# MRDT0002A1.net
KiCad netlist of a schematic drawn in EAGLE
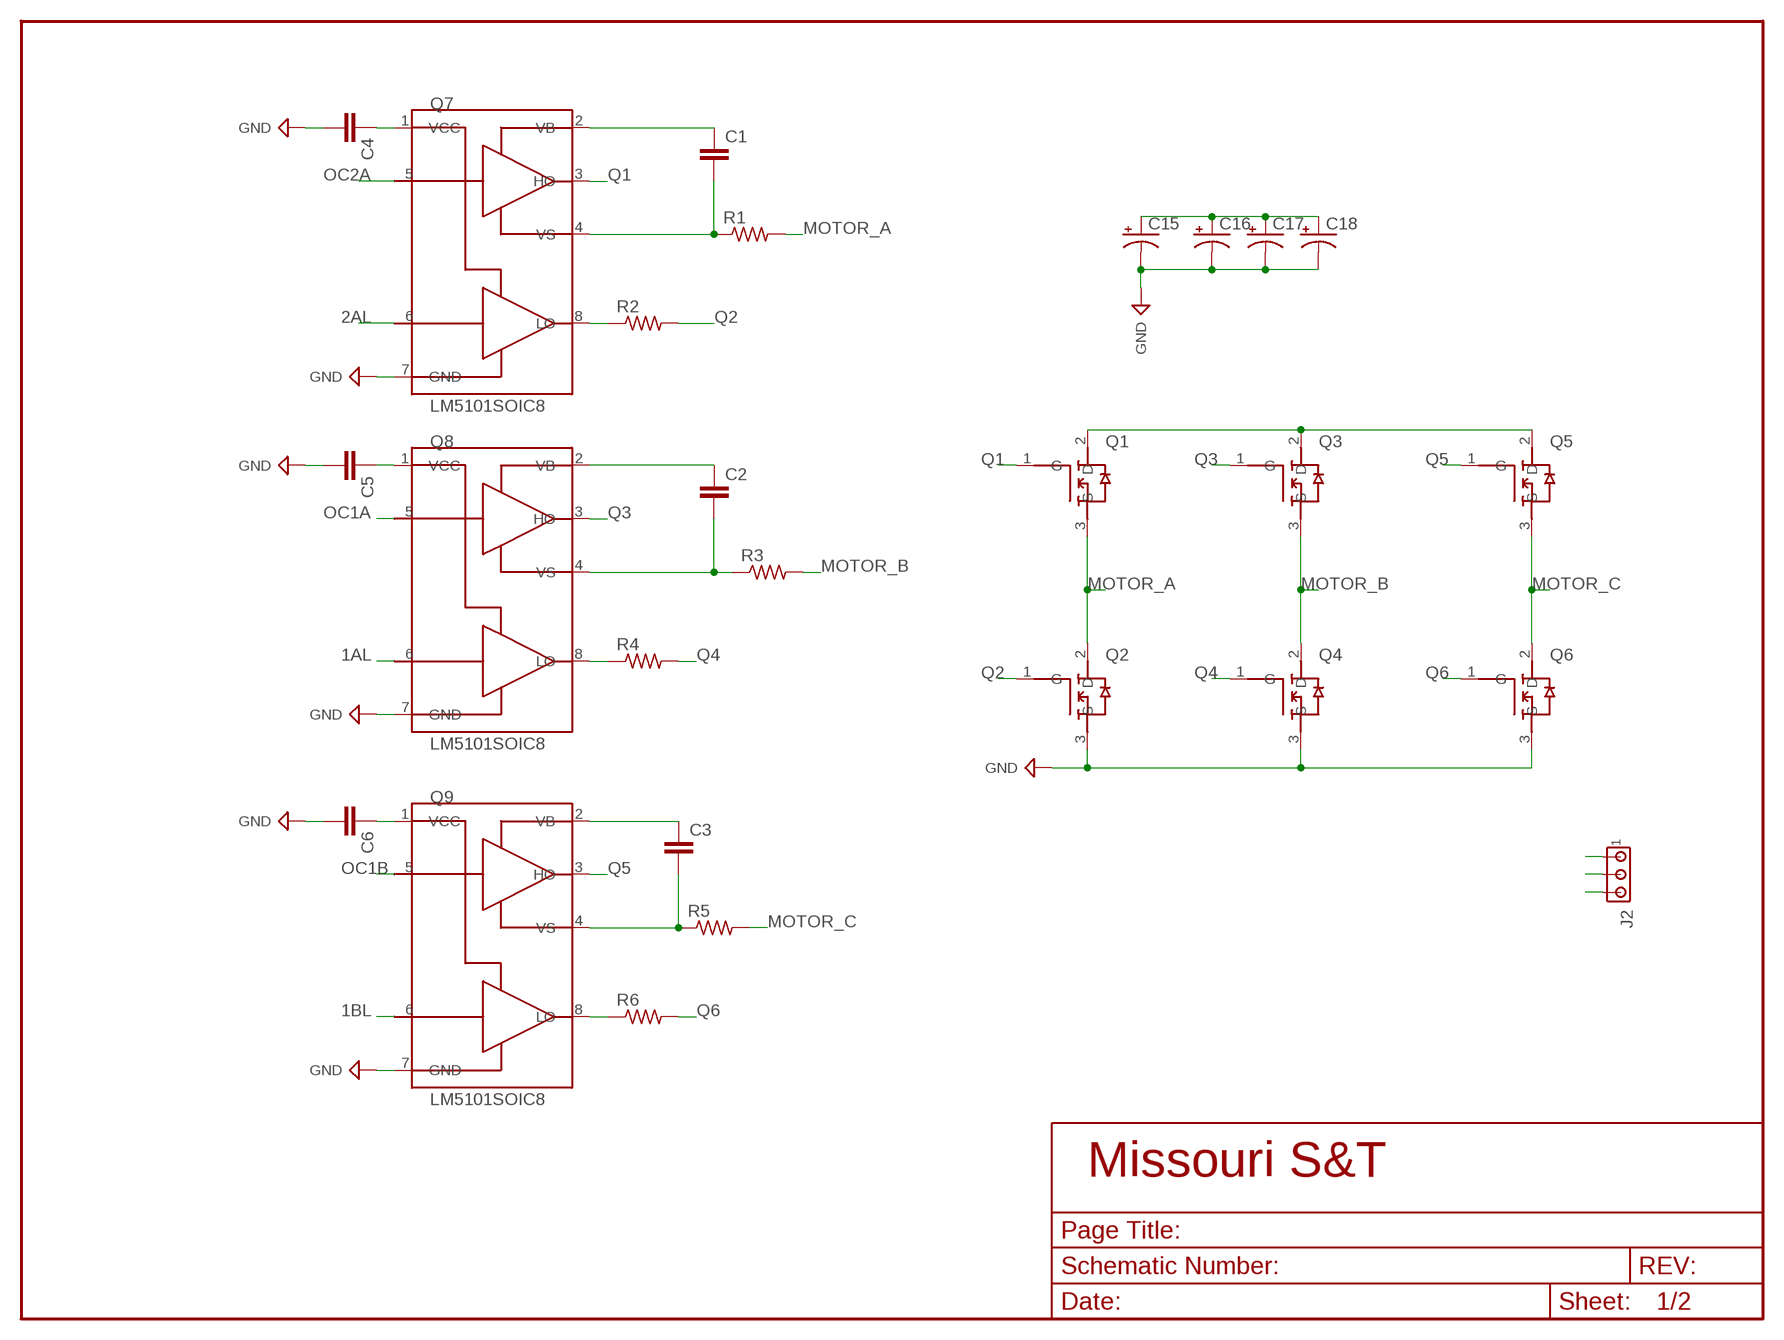
[diagram p0: schematic, sheet 1]
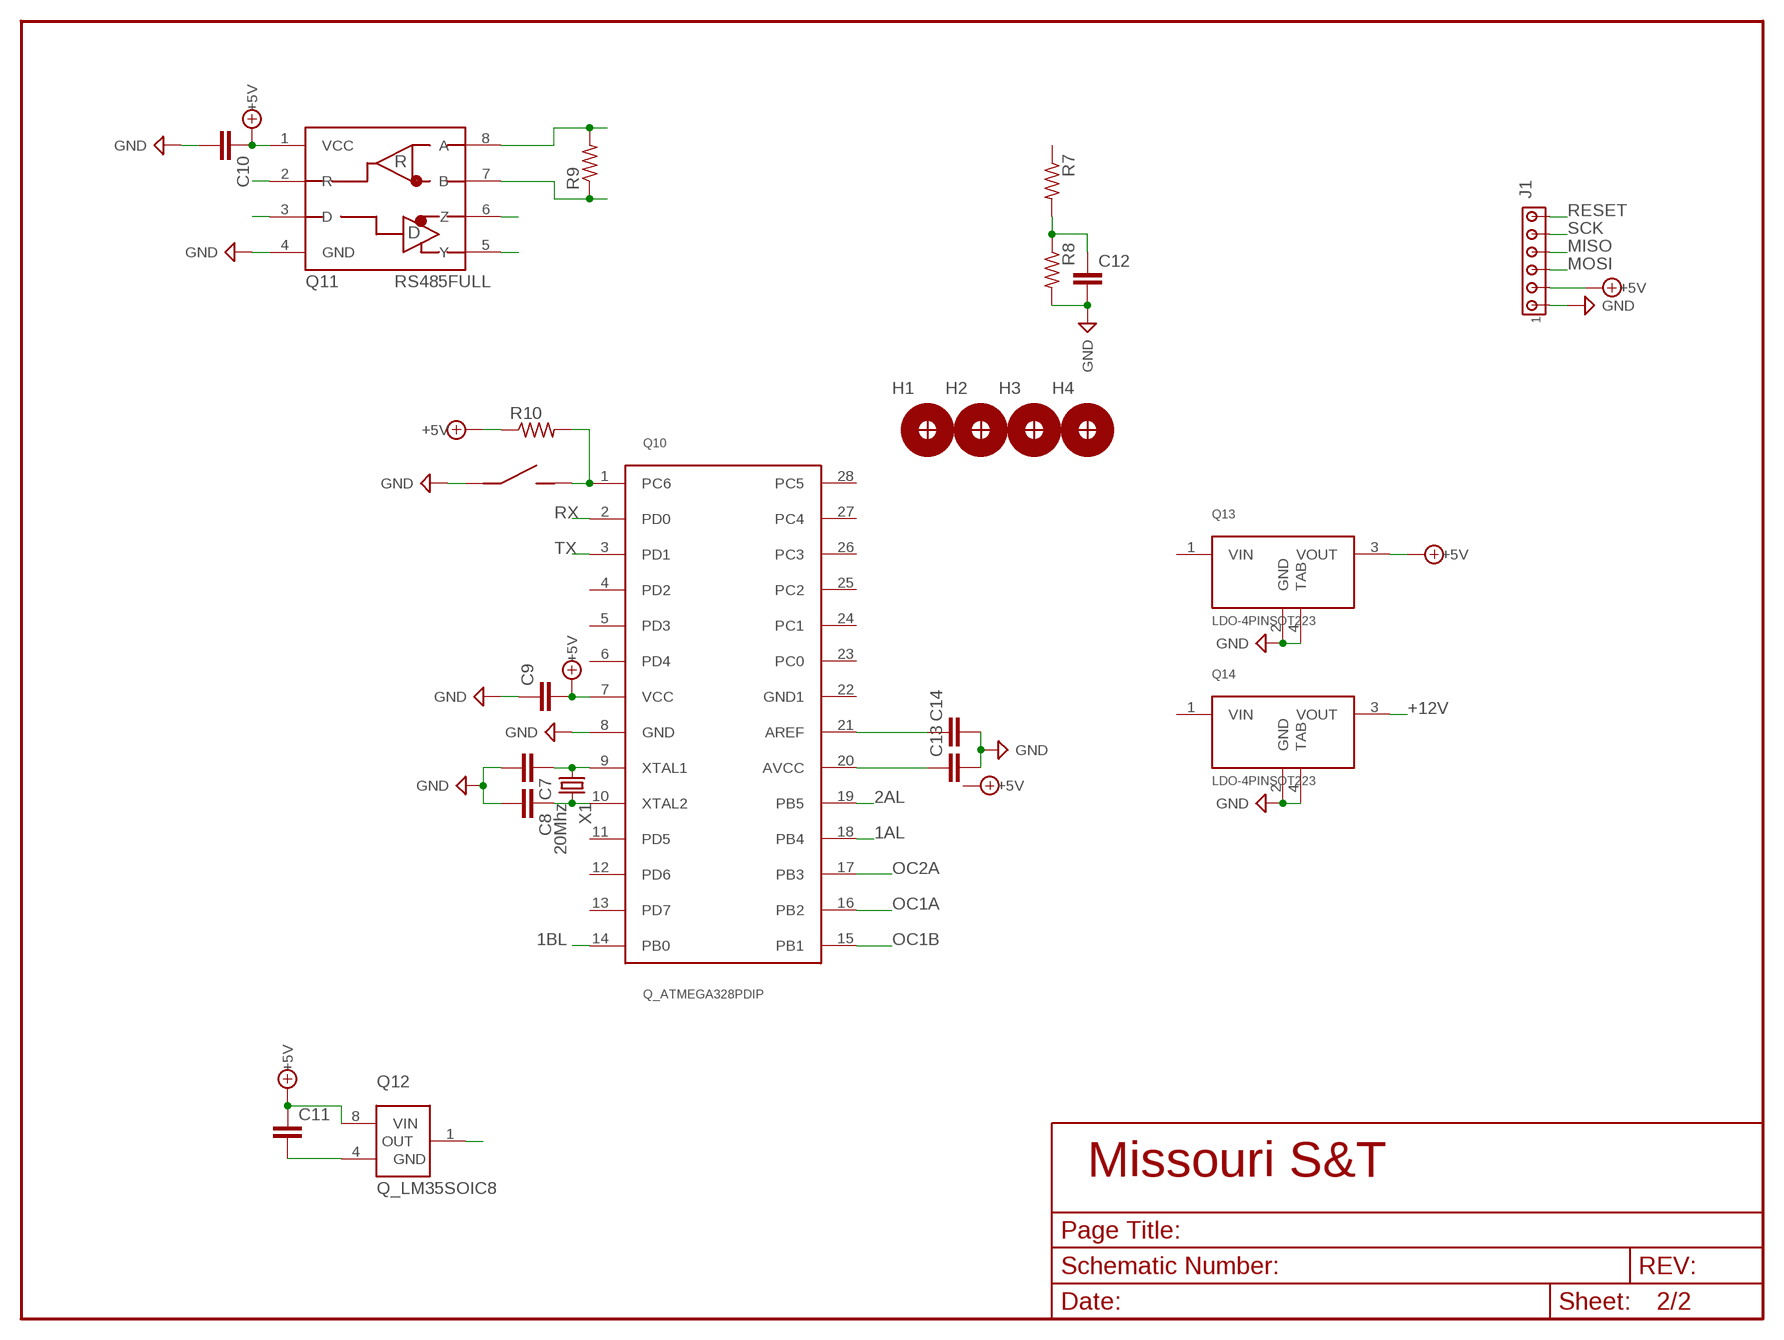
[diagram p1: schematic, sheet 2]

(export (version "E")
  (design (tool "Eeschema 10.0.6"))
  (components
    (comp (ref "C7")
      (value "C_CAP_1206")
      (footprint "eagle-import:C_1206")
      (libsource (lib "eagle-import") (part "C_CAP_1206"))
    )
    (comp (ref "C8")
      (value "C_CAP_1206")
      (footprint "eagle-import:C_1206")
      (libsource (lib "eagle-import") (part "C_CAP_1206"))
    )
    (comp (ref "C9")
      (value "C_CAP_0805")
      (footprint "eagle-import:C_0805")
      (libsource (lib "eagle-import") (part "C_CAP_0805"))
    )
    (comp (ref "C10")
      (value "C_CAP_0805")
      (footprint "eagle-import:C_0805")
      (libsource (lib "eagle-import") (part "C_CAP_0805"))
    )
    (comp (ref "C11")
      (value "C_CAP_0805")
      (footprint "eagle-import:C_0805")
      (libsource (lib "eagle-import") (part "C_CAP_0805"))
    )
    (comp (ref "C12")
      (value "C_CAP_0805")
      (footprint "eagle-import:C_0805")
      (libsource (lib "eagle-import") (part "C_CAP_0805"))
    )
    (comp (ref "C13")
      (value "C_CAP_0805")
      (footprint "eagle-import:C_0805")
      (libsource (lib "eagle-import") (part "C_CAP_0805"))
    )
    (comp (ref "C14")
      (value "C_CAP_0805")
      (footprint "eagle-import:C_0805")
      (libsource (lib "eagle-import") (part "C_CAP_0805"))
    )
    (comp (ref "H1")
      (value "H_MNTHOLE_#4")
      (footprint "eagle-import:H_MNTHOLE_#4")
      (libsource (lib "eagle-import") (part "H_MNTHOLE_#4"))
    )
    (comp (ref "H2")
      (value "H_MNTHOLE_#4")
      (footprint "eagle-import:H_MNTHOLE_#4")
      (libsource (lib "eagle-import") (part "H_MNTHOLE_#4"))
    )
    (comp (ref "H3")
      (value "H_MNTHOLE_#4")
      (footprint "eagle-import:H_MNTHOLE_#4")
      (libsource (lib "eagle-import") (part "H_MNTHOLE_#4"))
    )
    (comp (ref "H4")
      (value "H_MNTHOLE_#4")
      (footprint "eagle-import:H_MNTHOLE_#4")
      (libsource (lib "eagle-import") (part "H_MNTHOLE_#4"))
    )
    (comp (ref "J1")
      (value "J_MTA6P_100")
      (footprint "eagle-import:J_MTA100_6P")
      (libsource (lib "eagle-import") (part "J_MTA6P_100"))
    )
    (comp (ref "J3")
      (value "J_MC32857")
      (footprint "eagle-import:J_TOGGLE")
      (libsource (lib "eagle-import") (part "J_MC32857"))
    )
    (comp (ref "Q10")
      (value "Q_ATMEGA328PDIP")
      (footprint "eagle-import:DIP28")
      (libsource (lib "eagle-import") (part "Q_ATMEGA328PDIP"))
    )
    (comp (ref "Q11")
      (value "RS485FULL")
      (footprint "eagle-import:SOIC8")
      (libsource (lib "eagle-import") (part "RS485FULL"))
    )
    (comp (ref "Q12")
      (value "Q_LM35SOIC8")
      (footprint "eagle-import:SOIC8")
      (libsource (lib "eagle-import") (part "Q_LM35SOIC8"))
    )
    (comp (ref "Q13")
      (value "LDO-4PINSOT223")
      (footprint "eagle-import:SOT-223")
      (libsource (lib "eagle-import") (part "LDO-4PINSOT223"))
    )
    (comp (ref "Q14")
      (value "LDO-4PINSOT223")
      (footprint "eagle-import:SOT-223")
      (libsource (lib "eagle-import") (part "LDO-4PINSOT223"))
    )
    (comp (ref "R7")
      (value "R_RES_0805")
      (footprint "eagle-import:R_0805")
      (libsource (lib "eagle-import") (part "Master_R_RES_0805"))
    )
    (comp (ref "R8")
      (value "R_RES_0805")
      (footprint "eagle-import:R_0805")
      (libsource (lib "eagle-import") (part "Master_R_RES_0805"))
    )
    (comp (ref "R9")
      (value "R_RES_0805")
      (footprint "eagle-import:R_0805")
      (libsource (lib "eagle-import") (part "Master_R_RES_0805"))
    )
    (comp (ref "R10")
      (value "R_RES_0805")
      (footprint "eagle-import:R_0805")
      (libsource (lib "eagle-import") (part "R_RES_0805"))
    )
    (comp (ref "X1")
      (value "20Mhz")
      (footprint "eagle-import:HC-49")
      (libsource (lib "eagle-import") (part "X_HC49SCRYSTALTH"))
    )
    (comp (ref "C1")
      (value "C_CAP_1206")
      (footprint "eagle-import:C_1206")
      (libsource (lib "eagle-import") (part "C_CAP_1206"))
    )
    (comp (ref "C2")
      (value "C_CAP_1206")
      (footprint "eagle-import:C_1206")
      (libsource (lib "eagle-import") (part "C_CAP_1206"))
    )
    (comp (ref "C3")
      (value "C_CAP_1206")
      (footprint "eagle-import:C_1206")
      (libsource (lib "eagle-import") (part "C_CAP_1206"))
    )
    (comp (ref "C4")
      (value "C_CAP_1206")
      (footprint "eagle-import:C_1206")
      (libsource (lib "eagle-import") (part "C_CAP_1206"))
    )
    (comp (ref "C5")
      (value "C_CAP_1206")
      (footprint "eagle-import:C_1206")
      (libsource (lib "eagle-import") (part "C_CAP_1206"))
    )
    (comp (ref "C6")
      (value "C_CAP_1206")
      (footprint "eagle-import:C_1206")
      (libsource (lib "eagle-import") (part "C_CAP_1206"))
    )
    (comp (ref "C15")
      (value "CAP_POL10MMSM")
      (footprint "eagle-import:C_10MMSM")
      (libsource (lib "eagle-import") (part "CAP_POL10MMSM"))
    )
    (comp (ref "C16")
      (value "CAP_POL10MMSM")
      (footprint "eagle-import:C_10MMSM")
      (libsource (lib "eagle-import") (part "CAP_POL10MMSM"))
    )
    (comp (ref "C17")
      (value "CAP_POL10MMSM")
      (footprint "eagle-import:C_10MMSM")
      (libsource (lib "eagle-import") (part "CAP_POL10MMSM"))
    )
    (comp (ref "C18")
      (value "CAP_POL10MMSM")
      (footprint "eagle-import:C_10MMSM")
      (libsource (lib "eagle-import") (part "CAP_POL10MMSM"))
    )
    (comp (ref "J2")
      (value "J_MTA3P_156")
      (footprint "eagle-import:J_MTA156_3P")
      (libsource (lib "eagle-import") (part "J_MTA3P_156"))
    )
    (comp (ref "Q1")
      (value "N-CH-MOSFETTO252")
      (footprint "eagle-import:TO-252")
      (libsource (lib "eagle-import") (part "N-CH-MOSFETTO252"))
    )
    (comp (ref "Q2")
      (value "N-CH-MOSFETTO252")
      (footprint "eagle-import:TO-252")
      (libsource (lib "eagle-import") (part "N-CH-MOSFETTO252"))
    )
    (comp (ref "Q3")
      (value "N-CH-MOSFETTO252")
      (footprint "eagle-import:TO-252")
      (libsource (lib "eagle-import") (part "N-CH-MOSFETTO252"))
    )
    (comp (ref "Q4")
      (value "N-CH-MOSFETTO252")
      (footprint "eagle-import:TO-252")
      (libsource (lib "eagle-import") (part "N-CH-MOSFETTO252"))
    )
    (comp (ref "Q5")
      (value "N-CH-MOSFETTO252")
      (footprint "eagle-import:TO-252")
      (libsource (lib "eagle-import") (part "N-CH-MOSFETTO252"))
    )
    (comp (ref "Q6")
      (value "N-CH-MOSFETTO252")
      (footprint "eagle-import:TO-252")
      (libsource (lib "eagle-import") (part "N-CH-MOSFETTO252"))
    )
    (comp (ref "Q7")
      (value "LM5101SOIC8")
      (footprint "eagle-import:SOIC8")
      (libsource (lib "eagle-import") (part "LM5101SOIC8"))
    )
    (comp (ref "Q8")
      (value "LM5101SOIC8")
      (footprint "eagle-import:SOIC8")
      (libsource (lib "eagle-import") (part "LM5101SOIC8"))
    )
    (comp (ref "Q9")
      (value "LM5101SOIC8")
      (footprint "eagle-import:SOIC8")
      (libsource (lib "eagle-import") (part "LM5101SOIC8"))
    )
    (comp (ref "R1")
      (value "R_RES_0805")
      (footprint "eagle-import:R_0805")
      (libsource (lib "eagle-import") (part "Master_R_RES_0805"))
    )
    (comp (ref "R2")
      (value "R_RES_0805")
      (footprint "eagle-import:R_0805")
      (libsource (lib "eagle-import") (part "Master_R_RES_0805"))
    )
    (comp (ref "R3")
      (value "R_RES_0805")
      (footprint "eagle-import:R_0805")
      (libsource (lib "eagle-import") (part "Master_R_RES_0805"))
    )
    (comp (ref "R4")
      (value "R_RES_0805")
      (footprint "eagle-import:R_0805")
      (libsource (lib "eagle-import") (part "Master_R_RES_0805"))
    )
    (comp (ref "R5")
      (value "R_RES_0805")
      (footprint "eagle-import:R_0805")
      (libsource (lib "eagle-import") (part "Master_R_RES_0805"))
    )
    (comp (ref "R6")
      (value "R_RES_0805")
      (footprint "eagle-import:R_0805")
      (libsource (lib "eagle-import") (part "Master_R_RES_0805"))
    )
  )
  (nets
    (net (code "1") (name "+5V") (class "Default")
      (node (ref "C10") (pin "1") (pinfunction "1_1") (pintype "passive"))
      (node (ref "C11") (pin "1") (pinfunction "1_1") (pintype "passive"))
      (node (ref "C9") (pin "2") (pinfunction "2_2") (pintype "passive"))
      (node (ref "J1") (pin "2") (pinfunction "2_2") (pintype "passive"))
      (node (ref "Q10") (pin "7") (pinfunction "VCC_7") (pintype "bidirectional"))
      (node (ref "Q11") (pin "1") (pinfunction "VCC_1") (pintype "bidirectional"))
      (node (ref "Q12") (pin "8") (pinfunction "VIN_8") (pintype "bidirectional"))
      (node (ref "Q13") (pin "3") (pinfunction "VOUT_3") (pintype "bidirectional"))
      (node (ref "R10") (pin "1") (pinfunction "1_1") (pintype "passive"))
    )
    (net (code "2") (name "+12V") (class "Default")
      (node (ref "C4") (pin "1") (pinfunction "1_1") (pintype "passive"))
      (node (ref "C5") (pin "1") (pinfunction "1_1") (pintype "passive"))
      (node (ref "C6") (pin "1") (pinfunction "1_1") (pintype "passive"))
      (node (ref "Q14") (pin "3") (pinfunction "VOUT_3") (pintype "bidirectional"))
      (node (ref "Q7") (pin "1") (pinfunction "VCC_1") (pintype "bidirectional"))
      (node (ref "Q8") (pin "1") (pinfunction "VCC_1") (pintype "bidirectional"))
      (node (ref "Q9") (pin "1") (pinfunction "VCC_1") (pintype "bidirectional"))
    )
    (net (code "3") (name "+24V") (class "Default")
      (node (ref "C15") (pin "+") (pinfunction "+_+") (pintype "passive"))
      (node (ref "C16") (pin "+") (pinfunction "+_+") (pintype "passive"))
      (node (ref "C17") (pin "+") (pinfunction "+_+") (pintype "passive"))
      (node (ref "C18") (pin "+") (pinfunction "+_+") (pintype "passive"))
      (node (ref "Q1") (pin "2") (pinfunction "D_2") (pintype "bidirectional"))
      (node (ref "Q3") (pin "2") (pinfunction "D_2") (pintype "bidirectional"))
      (node (ref "Q5") (pin "2") (pinfunction "D_2") (pintype "bidirectional"))
    )
    (net (code "4") (name "1AL") (class "Default")
      (node (ref "Q10") (pin "18") (pinfunction "PB4_18") (pintype "bidirectional"))
      (node (ref "Q8") (pin "6") (pinfunction "LI_6") (pintype "bidirectional"))
    )
    (net (code "5") (name "1BL") (class "Default")
      (node (ref "Q10") (pin "14") (pinfunction "PB0_14") (pintype "bidirectional"))
      (node (ref "Q9") (pin "6") (pinfunction "LI_6") (pintype "bidirectional"))
    )
    (net (code "6") (name "2AL") (class "Default")
      (node (ref "Q10") (pin "19") (pinfunction "PB5_19") (pintype "bidirectional"))
      (node (ref "Q7") (pin "6") (pinfunction "LI_6") (pintype "bidirectional"))
    )
    (net (code "7") (name "GND") (class "Default")
      (node (ref "C10") (pin "2") (pinfunction "2_2") (pintype "passive"))
      (node (ref "C12") (pin "2") (pinfunction "2_2") (pintype "passive"))
      (node (ref "C13") (pin "2") (pinfunction "2_2") (pintype "passive"))
      (node (ref "C14") (pin "2") (pinfunction "2_2") (pintype "passive"))
      (node (ref "C15") (pin "-") (pinfunction "-_-") (pintype "passive"))
      (node (ref "C16") (pin "-") (pinfunction "-_-") (pintype "passive"))
      (node (ref "C17") (pin "-") (pinfunction "-_-") (pintype "passive"))
      (node (ref "C18") (pin "-") (pinfunction "-_-") (pintype "passive"))
      (node (ref "C4") (pin "2") (pinfunction "2_2") (pintype "passive"))
      (node (ref "C5") (pin "2") (pinfunction "2_2") (pintype "passive"))
      (node (ref "C6") (pin "2") (pinfunction "2_2") (pintype "passive"))
      (node (ref "C7") (pin "2") (pinfunction "2_2") (pintype "passive"))
      (node (ref "C8") (pin "2") (pinfunction "2_2") (pintype "passive"))
      (node (ref "C9") (pin "1") (pinfunction "1_1") (pintype "passive"))
      (node (ref "J1") (pin "1") (pinfunction "1_1") (pintype "passive"))
      (node (ref "J3") (pin "P$1") (pinfunction "1_P$1") (pintype "bidirectional"))
      (node (ref "Q10") (pin "8") (pinfunction "GND_8") (pintype "bidirectional"))
      (node (ref "Q11") (pin "4") (pinfunction "GND_4") (pintype "bidirectional"))
      (node (ref "Q13") (pin "2") (pinfunction "GND_2") (pintype "bidirectional"))
      (node (ref "Q13") (pin "4") (pinfunction "TAB_4") (pintype "bidirectional"))
      (node (ref "Q14") (pin "2") (pinfunction "GND_2") (pintype "bidirectional"))
      (node (ref "Q14") (pin "4") (pinfunction "TAB_4") (pintype "bidirectional"))
      (node (ref "Q2") (pin "3") (pinfunction "S_3") (pintype "bidirectional"))
      (node (ref "Q4") (pin "3") (pinfunction "S_3") (pintype "bidirectional"))
      (node (ref "Q6") (pin "3") (pinfunction "S_3") (pintype "bidirectional"))
      (node (ref "Q7") (pin "7") (pinfunction "GND_7") (pintype "bidirectional"))
      (node (ref "Q8") (pin "7") (pinfunction "GND_7") (pintype "bidirectional"))
      (node (ref "Q9") (pin "7") (pinfunction "GND_7") (pintype "bidirectional"))
      (node (ref "R8") (pin "2") (pinfunction "2_2") (pintype "passive"))
    )
    (net (code "8") (name "MISO") (class "Default")
      (node (ref "J1") (pin "4") (pinfunction "4_4") (pintype "passive"))
    )
    (net (code "9") (name "MOSI") (class "Default")
      (node (ref "J1") (pin "3") (pinfunction "3_3") (pintype "passive"))
    )
    (net (code "10") (name "MOTOR_A") (class "Default")
      (node (ref "J2") (pin "3") (pinfunction "3_3") (pintype "passive"))
      (node (ref "Q1") (pin "3") (pinfunction "S_3") (pintype "bidirectional"))
      (node (ref "Q2") (pin "2") (pinfunction "D_2") (pintype "bidirectional"))
      (node (ref "R1") (pin "2") (pinfunction "2_2") (pintype "passive"))
    )
    (net (code "11") (name "MOTOR_B") (class "Default")
      (node (ref "J2") (pin "2") (pinfunction "2_2") (pintype "passive"))
      (node (ref "Q3") (pin "3") (pinfunction "S_3") (pintype "bidirectional"))
      (node (ref "Q4") (pin "2") (pinfunction "D_2") (pintype "bidirectional"))
      (node (ref "R3") (pin "2") (pinfunction "2_2") (pintype "passive"))
    )
    (net (code "12") (name "MOTOR_C") (class "Default")
      (node (ref "J2") (pin "1") (pinfunction "1_1") (pintype "passive"))
      (node (ref "Q5") (pin "3") (pinfunction "S_3") (pintype "bidirectional"))
      (node (ref "Q6") (pin "2") (pinfunction "D_2") (pintype "bidirectional"))
      (node (ref "R5") (pin "2") (pinfunction "2_2") (pintype "passive"))
    )
    (net (code "13") (name "Net-(C12-Pad1)") (class "Default")
      (node (ref "C12") (pin "1") (pinfunction "1_1") (pintype "passive"))
      (node (ref "R7") (pin "2") (pinfunction "2_2") (pintype "passive"))
      (node (ref "R8") (pin "1") (pinfunction "1_1") (pintype "passive"))
    )
    (net (code "14") (name "Net-(J3-2)") (class "Default")
      (node (ref "J3") (pin "P$2") (pinfunction "2_P$2") (pintype "bidirectional"))
      (node (ref "Q10") (pin "1") (pinfunction "PC6_1") (pintype "bidirectional"))
      (node (ref "R10") (pin "2") (pinfunction "2_2") (pintype "passive"))
    )
    (net (code "15") (name "Net-(Q7-LO)") (class "Default")
      (node (ref "Q7") (pin "8") (pinfunction "LO_8") (pintype "bidirectional"))
      (node (ref "R2") (pin "1") (pinfunction "1_1") (pintype "passive"))
    )
    (net (code "16") (name "Net-(Q7-VB)") (class "Default")
      (node (ref "C1") (pin "1") (pinfunction "1_1") (pintype "passive"))
      (node (ref "Q7") (pin "2") (pinfunction "VB_2") (pintype "bidirectional"))
    )
    (net (code "17") (name "Net-(Q7-VS)") (class "Default")
      (node (ref "C1") (pin "2") (pinfunction "2_2") (pintype "passive"))
      (node (ref "Q7") (pin "4") (pinfunction "VS_4") (pintype "bidirectional"))
      (node (ref "R1") (pin "1") (pinfunction "1_1") (pintype "passive"))
    )
    (net (code "18") (name "Net-(Q8-LO)") (class "Default")
      (node (ref "Q8") (pin "8") (pinfunction "LO_8") (pintype "bidirectional"))
      (node (ref "R4") (pin "1") (pinfunction "1_1") (pintype "passive"))
    )
    (net (code "19") (name "Net-(Q8-VB)") (class "Default")
      (node (ref "C2") (pin "1") (pinfunction "1_1") (pintype "passive"))
      (node (ref "Q8") (pin "2") (pinfunction "VB_2") (pintype "bidirectional"))
    )
    (net (code "20") (name "Net-(Q8-VS)") (class "Default")
      (node (ref "C2") (pin "2") (pinfunction "2_2") (pintype "passive"))
      (node (ref "Q8") (pin "4") (pinfunction "VS_4") (pintype "bidirectional"))
      (node (ref "R3") (pin "1") (pinfunction "1_1") (pintype "passive"))
    )
    (net (code "21") (name "Net-(Q9-LO)") (class "Default")
      (node (ref "Q9") (pin "8") (pinfunction "LO_8") (pintype "bidirectional"))
      (node (ref "R6") (pin "1") (pinfunction "1_1") (pintype "passive"))
    )
    (net (code "22") (name "Net-(Q9-VB)") (class "Default")
      (node (ref "C3") (pin "1") (pinfunction "1_1") (pintype "passive"))
      (node (ref "Q9") (pin "2") (pinfunction "VB_2") (pintype "bidirectional"))
    )
    (net (code "23") (name "Net-(Q9-VS)") (class "Default")
      (node (ref "C3") (pin "2") (pinfunction "2_2") (pintype "passive"))
      (node (ref "Q9") (pin "4") (pinfunction "VS_4") (pintype "bidirectional"))
      (node (ref "R5") (pin "1") (pinfunction "1_1") (pintype "passive"))
    )
    (net (code "24") (name "Net-(Q10-AREF)") (class "Default")
      (node (ref "C14") (pin "1") (pinfunction "1_1") (pintype "passive"))
      (node (ref "Q10") (pin "21") (pinfunction "AREF_21") (pintype "bidirectional"))
    )
    (net (code "25") (name "Net-(Q10-AVCC)") (class "Default")
      (node (ref "C13") (pin "1") (pinfunction "1_1") (pintype "passive"))
      (node (ref "Q10") (pin "20") (pinfunction "AVCC_20") (pintype "bidirectional"))
    )
    (net (code "26") (name "Net-(Q10-XTAL1)") (class "Default")
      (node (ref "C7") (pin "1") (pinfunction "1_1") (pintype "passive"))
      (node (ref "Q10") (pin "9") (pinfunction "XTAL1_9") (pintype "bidirectional"))
      (node (ref "X1") (pin "P$1") (pinfunction "1_P$1") (pintype "passive"))
    )
    (net (code "27") (name "Net-(Q10-XTAL2)") (class "Default")
      (node (ref "C8") (pin "1") (pinfunction "1_1") (pintype "passive"))
      (node (ref "Q10") (pin "10") (pinfunction "XTAL2_10") (pintype "bidirectional"))
      (node (ref "X1") (pin "P$2") (pinfunction "2_P$2") (pintype "passive"))
    )
    (net (code "28") (name "Net-(Q11-A)") (class "Default")
      (node (ref "Q11") (pin "8") (pinfunction "A_8") (pintype "bidirectional"))
      (node (ref "R9") (pin "2") (pinfunction "2_2") (pintype "passive"))
    )
    (net (code "29") (name "Net-(Q11-B)") (class "Default")
      (node (ref "Q11") (pin "7") (pinfunction "B_7") (pintype "bidirectional"))
      (node (ref "R9") (pin "1") (pinfunction "1_1") (pintype "passive"))
    )
    (net (code "30") (name "Net-(Q12-GND)") (class "Default")
      (node (ref "C11") (pin "2") (pinfunction "2_2") (pintype "passive"))
      (node (ref "Q12") (pin "4") (pinfunction "GND_4") (pintype "bidirectional"))
    )
    (net (code "31") (name "OC1A") (class "Default")
      (node (ref "Q10") (pin "16") (pinfunction "PB2_16") (pintype "bidirectional"))
      (node (ref "Q8") (pin "5") (pinfunction "HI_5") (pintype "bidirectional"))
    )
    (net (code "32") (name "OC1B") (class "Default")
      (node (ref "Q10") (pin "15") (pinfunction "PB1_15") (pintype "bidirectional"))
      (node (ref "Q9") (pin "5") (pinfunction "HI_5") (pintype "bidirectional"))
    )
    (net (code "33") (name "OC2A") (class "Default")
      (node (ref "Q10") (pin "17") (pinfunction "PB3_17") (pintype "bidirectional"))
      (node (ref "Q7") (pin "5") (pinfunction "HI_5") (pintype "bidirectional"))
    )
    (net (code "34") (name "Q1") (class "Default")
      (node (ref "Q1") (pin "1") (pinfunction "G_1") (pintype "bidirectional"))
      (node (ref "Q7") (pin "3") (pinfunction "HO_3") (pintype "bidirectional"))
    )
    (net (code "35") (name "Q2") (class "Default")
      (node (ref "Q2") (pin "1") (pinfunction "G_1") (pintype "bidirectional"))
      (node (ref "R2") (pin "2") (pinfunction "2_2") (pintype "passive"))
    )
    (net (code "36") (name "Q3") (class "Default")
      (node (ref "Q3") (pin "1") (pinfunction "G_1") (pintype "bidirectional"))
      (node (ref "Q8") (pin "3") (pinfunction "HO_3") (pintype "bidirectional"))
    )
    (net (code "37") (name "Q4") (class "Default")
      (node (ref "Q4") (pin "1") (pinfunction "G_1") (pintype "bidirectional"))
      (node (ref "R4") (pin "2") (pinfunction "2_2") (pintype "passive"))
    )
    (net (code "38") (name "Q5") (class "Default")
      (node (ref "Q5") (pin "1") (pinfunction "G_1") (pintype "bidirectional"))
      (node (ref "Q9") (pin "3") (pinfunction "HO_3") (pintype "bidirectional"))
    )
    (net (code "39") (name "Q6") (class "Default")
      (node (ref "Q6") (pin "1") (pinfunction "G_1") (pintype "bidirectional"))
      (node (ref "R6") (pin "2") (pinfunction "2_2") (pintype "passive"))
    )
    (net (code "40") (name "RESET") (class "Default")
      (node (ref "J1") (pin "6") (pinfunction "6_6") (pintype "passive"))
    )
    (net (code "41") (name "RX") (class "Default")
      (node (ref "Q10") (pin "2") (pinfunction "PD0_2") (pintype "bidirectional"))
      (node (ref "Q11") (pin "2") (pinfunction "R_2") (pintype "bidirectional"))
    )
    (net (code "42") (name "SCK") (class "Default")
      (node (ref "J1") (pin "5") (pinfunction "5_5") (pintype "passive"))
    )
    (net (code "43") (name "TX") (class "Default")
      (node (ref "Q10") (pin "3") (pinfunction "PD1_3") (pintype "bidirectional"))
      (node (ref "Q11") (pin "3") (pinfunction "D_3") (pintype "bidirectional"))
    )
    (net (code "44") (name "unconnected-(H1-Pad1)") (class "Default")
      (node (ref "H1") (pin "1") (pinfunction "1_1") (pintype "passive"))
    )
    (net (code "45") (name "unconnected-(H2-Pad1)") (class "Default")
      (node (ref "H2") (pin "1") (pinfunction "1_1") (pintype "passive"))
    )
    (net (code "46") (name "unconnected-(H3-Pad1)") (class "Default")
      (node (ref "H3") (pin "1") (pinfunction "1_1") (pintype "passive"))
    )
    (net (code "47") (name "unconnected-(H4-Pad1)") (class "Default")
      (node (ref "H4") (pin "1") (pinfunction "1_1") (pintype "passive"))
    )
    (net (code "48") (name "unconnected-(Q10-GND1-Pad22)") (class "Default")
      (node (ref "Q10") (pin "22") (pinfunction "GND1_22") (pintype "bidirectional"))
    )
    (net (code "49") (name "unconnected-(Q10-PC0-Pad23)") (class "Default")
      (node (ref "Q10") (pin "23") (pinfunction "PC0_23") (pintype "bidirectional"))
    )
    (net (code "50") (name "unconnected-(Q10-PC1-Pad24)") (class "Default")
      (node (ref "Q10") (pin "24") (pinfunction "PC1_24") (pintype "bidirectional"))
    )
    (net (code "51") (name "unconnected-(Q10-PC2-Pad25)") (class "Default")
      (node (ref "Q10") (pin "25") (pinfunction "PC2_25") (pintype "bidirectional"))
    )
    (net (code "52") (name "unconnected-(Q10-PC3-Pad26)") (class "Default")
      (node (ref "Q10") (pin "26") (pinfunction "PC3_26") (pintype "bidirectional"))
    )
    (net (code "53") (name "unconnected-(Q10-PC4-Pad27)") (class "Default")
      (node (ref "Q10") (pin "27") (pinfunction "PC4_27") (pintype "bidirectional"))
    )
    (net (code "54") (name "unconnected-(Q10-PC5-Pad28)") (class "Default")
      (node (ref "Q10") (pin "28") (pinfunction "PC5_28") (pintype "bidirectional"))
    )
    (net (code "55") (name "unconnected-(Q10-PD2-Pad4)") (class "Default")
      (node (ref "Q10") (pin "4") (pinfunction "PD2_4") (pintype "bidirectional"))
    )
    (net (code "56") (name "unconnected-(Q10-PD3-Pad5)") (class "Default")
      (node (ref "Q10") (pin "5") (pinfunction "PD3_5") (pintype "bidirectional"))
    )
    (net (code "57") (name "unconnected-(Q10-PD4-Pad6)") (class "Default")
      (node (ref "Q10") (pin "6") (pinfunction "PD4_6") (pintype "bidirectional"))
    )
    (net (code "58") (name "unconnected-(Q10-PD5-Pad11)") (class "Default")
      (node (ref "Q10") (pin "11") (pinfunction "PD5_11") (pintype "bidirectional"))
    )
    (net (code "59") (name "unconnected-(Q10-PD6-Pad12)") (class "Default")
      (node (ref "Q10") (pin "12") (pinfunction "PD6_12") (pintype "bidirectional"))
    )
    (net (code "60") (name "unconnected-(Q10-PD7-Pad13)") (class "Default")
      (node (ref "Q10") (pin "13") (pinfunction "PD7_13") (pintype "bidirectional"))
    )
    (net (code "61") (name "unconnected-(Q11-Y-Pad5)") (class "Default")
      (node (ref "Q11") (pin "5") (pinfunction "Y_5") (pintype "bidirectional"))
    )
    (net (code "62") (name "unconnected-(Q11-Z-Pad6)") (class "Default")
      (node (ref "Q11") (pin "6") (pinfunction "Z_6") (pintype "bidirectional"))
    )
    (net (code "63") (name "unconnected-(Q12-OUT-Pad1)") (class "Default")
      (node (ref "Q12") (pin "1") (pinfunction "OUT_1") (pintype "bidirectional"))
    )
    (net (code "64") (name "unconnected-(Q13-VIN-Pad1)") (class "Default")
      (node (ref "Q13") (pin "1") (pinfunction "VIN_1") (pintype "bidirectional"))
    )
    (net (code "65") (name "unconnected-(Q14-VIN-Pad1)") (class "Default")
      (node (ref "Q14") (pin "1") (pinfunction "VIN_1") (pintype "bidirectional"))
    )
    (net (code "66") (name "unconnected-(R7-Pad1)") (class "Default")
      (node (ref "R7") (pin "1") (pinfunction "1_1") (pintype "passive"))
    )
  )
)
